# brushless.net
KiCad netlist of a schematic drawn in Altium Designer
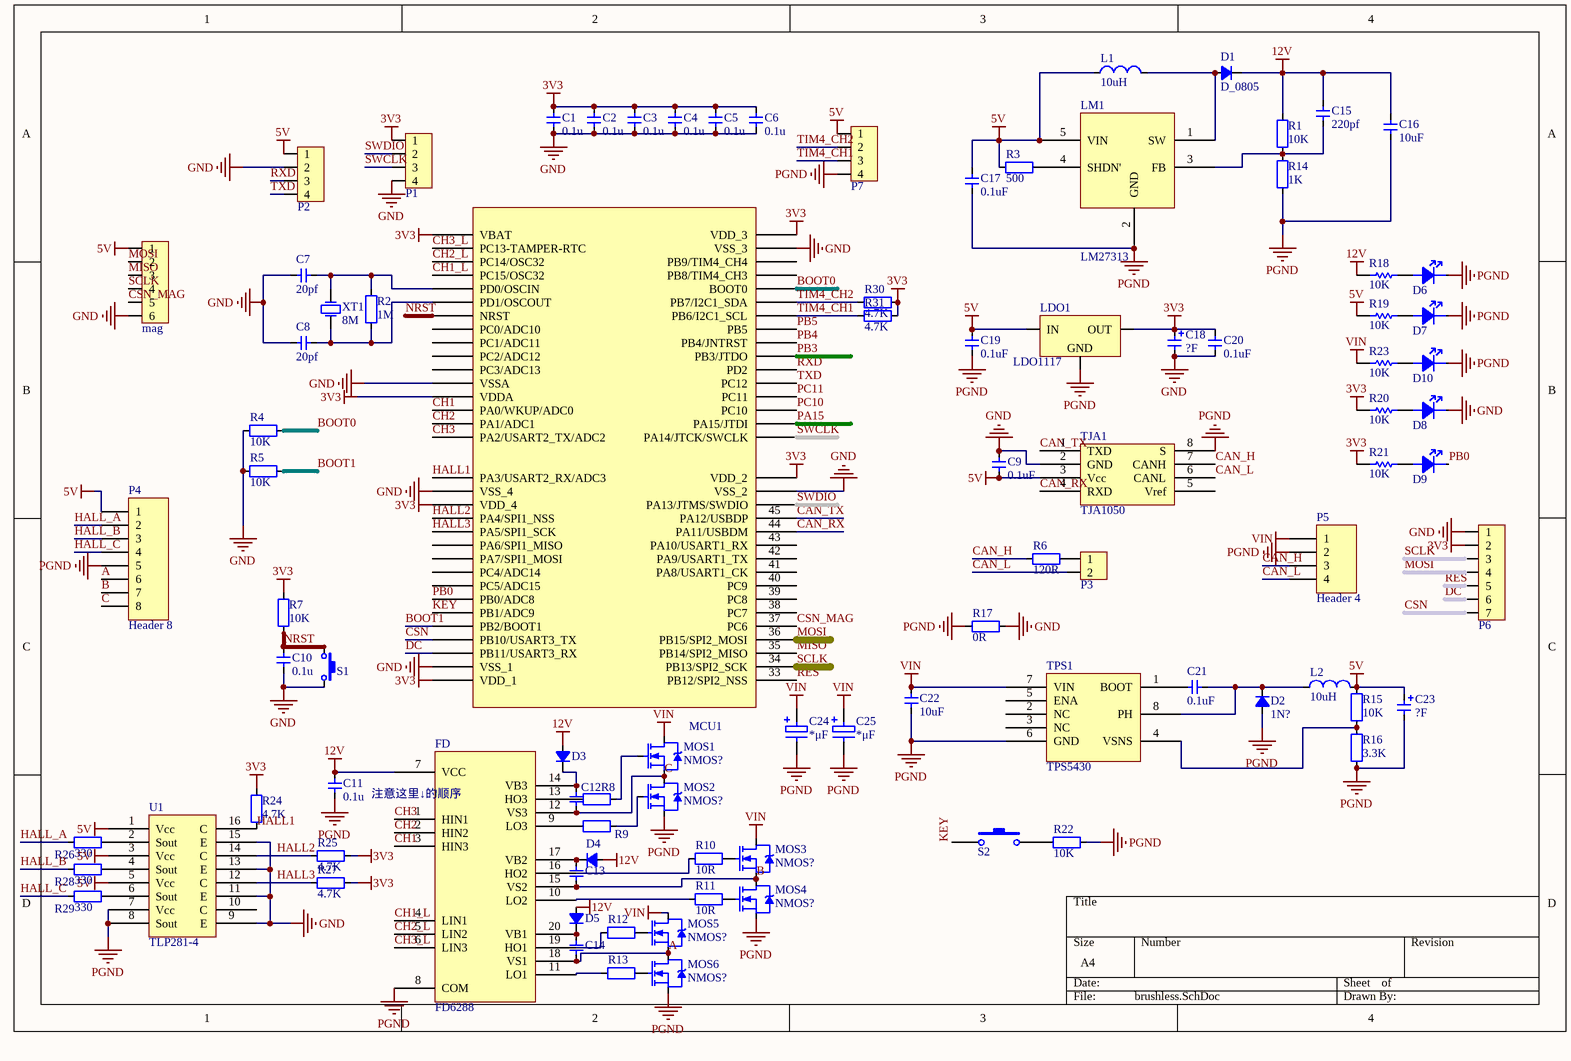
[diagram p0: brushless.SchDoc]

(export (version "E")
  (design (tool "Eeschema 10.0.6"))
  (components
    (comp (ref "C1")
      (value "0.1u")
      (footprint "PCB_PassiveCap:CAP_0603")
      (description "Capacitor")
      (fields (field (name "Comment") "Cap_0603"))
      (libsource (lib "SCH_Passive") (part "Cap_0603"))
    )
    (comp (ref "C2")
      (value "0.1u")
      (footprint "PCB_PassiveCap:CAP_0603")
      (description "Capacitor")
      (fields (field (name "Comment") "Cap_0603"))
      (libsource (lib "SCH_Passive") (part "Cap_0603"))
    )
    (comp (ref "C3")
      (value "0.1u")
      (footprint "PCB_PassiveCap:CAP_0603")
      (description "Capacitor")
      (fields (field (name "Comment") "Cap_0603"))
      (libsource (lib "SCH_Passive") (part "Cap_0603"))
    )
    (comp (ref "C4")
      (value "0.1u")
      (footprint "PCB_PassiveCap:CAP_0603")
      (description "Capacitor")
      (fields (field (name "Comment") "Cap_0603"))
      (libsource (lib "SCH_Passive") (part "Cap_0603"))
    )
    (comp (ref "C5")
      (value "0.1u")
      (footprint "PCB_PassiveCap:CAP_0603")
      (description "Capacitor")
      (fields (field (name "Comment") "Cap_0603"))
      (libsource (lib "SCH_Passive") (part "Cap_0603"))
    )
    (comp (ref "C6")
      (value "0.1u")
      (footprint "PCB_PassiveCap:CAP_0603")
      (description "Capacitor")
      (fields (field (name "Comment") "Cap_0603"))
      (libsource (lib "SCH_Passive") (part "Cap_0603"))
    )
    (comp (ref "C7")
      (value "20pf")
      (footprint "PCB_PassiveCap:CAP_0603")
      (description "Capacitor")
      (fields (field (name "Comment") "Cap_0603"))
      (libsource (lib "SCH_Passive") (part "Cap_0603"))
    )
    (comp (ref "C8")
      (value "20pf")
      (footprint "PCB_PassiveCap:CAP_0603")
      (description "Capacitor")
      (fields (field (name "Comment") "Cap_0603"))
      (libsource (lib "SCH_Passive") (part "Cap_0603"))
    )
    (comp (ref "C9")
      (value "0.1uF")
      (footprint "PCB_PassiveCap:CAP_0603")
      (description "Capacitor")
      (fields (field (name "Comment") "Cap_0603"))
      (libsource (lib "SCH_Passive") (part "Cap_0603"))
    )
    (comp (ref "C10")
      (value "0.1u")
      (footprint "PCB_PassiveCap:CAP_0603")
      (description "Capacitor")
      (fields (field (name "Comment") "Cap_0603"))
      (libsource (lib "SCH_Passive") (part "Cap_0603"))
    )
    (comp (ref "C11")
      (value "0.1u")
      (footprint "PCB_PassiveCap:CAP_0603")
      (description "Capacitor")
      (fields (field (name "Comment") "Cap_0603"))
      (libsource (lib "SCH_Passive") (part "Cap_0603"))
    )
    (comp (ref "C12")
      (value "Cap_0603")
      (footprint "PCB_PassiveCap:CAP_0603")
      (description "Capacitor")
      (libsource (lib "SCH_Passive") (part "Cap_0603"))
    )
    (comp (ref "C13")
      (value "Cap_0603")
      (footprint "PCB_PassiveCap:CAP_0603")
      (description "Capacitor")
      (libsource (lib "SCH_Passive") (part "Cap_0603"))
    )
    (comp (ref "C14")
      (value "Cap_0603")
      (footprint "PCB_PassiveCap:CAP_0603")
      (description "Capacitor")
      (libsource (lib "SCH_Passive") (part "Cap_0603"))
    )
    (comp (ref "C15")
      (value "220pf")
      (footprint "PCB_PassiveCap:CAP_0603")
      (description "Capacitor")
      (fields (field (name "Comment") "Cap_0603"))
      (libsource (lib "SCH_Passive") (part "Cap_0603"))
    )
    (comp (ref "C16")
      (value "10uF")
      (footprint "PCB_PassiveCap:CAP_0603")
      (description "Capacitor")
      (fields (field (name "Comment") "Cap_0603"))
      (libsource (lib "SCH_Passive") (part "Cap_0603"))
    )
    (comp (ref "C17")
      (value "0.1uF")
      (footprint "PCB_PassiveCap:CAP_0603")
      (description "Capacitor")
      (fields (field (name "Comment") "Cap_0603"))
      (libsource (lib "SCH_Passive") (part "Cap_0603"))
    )
    (comp (ref "C18")
      (value "?F")
      (footprint "PCB_PassiveCap:CAP_TAN_D2917")
      (description "Capacitor")
      (fields (field (name "Comment") "Cap_Tan_2917"))
      (libsource (lib "SCH_Passive") (part "Cap_Tan_2917"))
    )
    (comp (ref "C19")
      (value "0.1uF")
      (footprint "PCB_PassiveCap:CAP_0603")
      (description "Capacitor")
      (fields (field (name "Comment") "Cap_0603"))
      (libsource (lib "SCH_Passive") (part "Cap_0603"))
    )
    (comp (ref "C20")
      (value "0.1uF")
      (footprint "PCB_PassiveCap:CAP_0603")
      (description "Capacitor")
      (fields (field (name "Comment") "Cap_0603"))
      (libsource (lib "SCH_Passive") (part "Cap_0603"))
    )
    (comp (ref "C21")
      (value "0.1uF")
      (footprint "PCB_PassiveCap:CAP_0603")
      (description "Capacitor")
      (fields (field (name "Comment") "Cap_0603"))
      (libsource (lib "SCH_Passive") (part "Cap_0603"))
    )
    (comp (ref "C22")
      (value "10uF")
      (footprint "PCB_PassiveCap:CAP_0603")
      (description "Capacitor")
      (fields (field (name "Comment") "Cap_0603"))
      (libsource (lib "SCH_Passive") (part "Cap_0603"))
    )
    (comp (ref "C23")
      (value "?F")
      (footprint "PCB_PassiveCap:CAP_TAN_D2917")
      (description "Capacitor")
      (fields (field (name "Comment") "Cap_Tan_2917"))
      (libsource (lib "SCH_Passive") (part "Cap_Tan_2917"))
    )
    (comp (ref "C24")
      (value "*μF")
      (footprint "C_ELE2")
      (description "电解电容")
      (fields (field (name "PUBLISHER") "Altium Limited"))
      (libsource (lib "Libraries_2014_0618") (part "CAP-ELE"))
    )
    (comp (ref "C25")
      (value "*μF")
      (footprint "C_ELE2")
      (description "电解电容")
      (fields (field (name "PUBLISHER") "Altium Limited"))
      (libsource (lib "Libraries_2014_0618") (part "CAP-ELE"))
    )
    (comp (ref "D1")
      (value "D_0805")
      (footprint "LED_0805_YELLOW")
      (libsource (lib "SCH_Active") (part "D_0805"))
    )
    (comp (ref "D2")
      (value "1N?")
      (footprint "PCB_ActiveDIO:DO-214AC")
      (description "Diode")
      (fields (field (name "Comment") "Diode_SMA"))
      (libsource (lib "SCH_Active") (part "Diode_SMA"))
    )
    (comp (ref "D3")
      (value "D_0805")
      (footprint "LED_0805_YELLOW")
      (libsource (lib "SCH_Active") (part "D_0805"))
    )
    (comp (ref "D4")
      (value "D_0805")
      (footprint "LED_0805_YELLOW")
      (libsource (lib "SCH_Active") (part "D_0805"))
    )
    (comp (ref "D5")
      (value "D_0805")
      (footprint "LED_0805_YELLOW")
      (libsource (lib "SCH_Active") (part "D_0805"))
    )
    (comp (ref "D6")
      (value "lED")
      (footprint "0805D")
      (description "LED")
      (libsource (lib "K60-mainboard-v3.1") (part "00-D-LED"))
    )
    (comp (ref "D7")
      (value "lED")
      (footprint "0805D")
      (description "LED")
      (libsource (lib "K60-mainboard-v3.1") (part "00-D-LED"))
    )
    (comp (ref "D8")
      (value "lED")
      (footprint "0805D")
      (description "LED")
      (libsource (lib "K60-mainboard-v3.1") (part "00-D-LED"))
    )
    (comp (ref "D9")
      (value "lED")
      (footprint "0805D")
      (description "LED")
      (libsource (lib "K60-mainboard-v3.1") (part "00-D-LED"))
    )
    (comp (ref "D10")
      (value "lED")
      (footprint "0805D")
      (description "LED")
      (libsource (lib "K60-mainboard-v3.1") (part "00-D-LED"))
    )
    (comp (ref "FD")
      (value "FD6288")
      (footprint "TSSOP_E170_P0.65_20")
      (libsource (lib "SCH_IntegratedCircuit") (part "FD6288"))
    )
    (comp (ref "L1")
      (value "10uH")
      (footprint "IND_CD52")
      (description "Inductor")
      (fields (field (name "Comment") "Ind_CD32"))
      (libsource (lib "SCH_Passive") (part "Ind_CD32"))
    )
    (comp (ref "L2")
      (value "10uH")
      (footprint "IND_CD52")
      (description "Inductor")
      (fields (field (name "Comment") "Ind_CD32"))
      (libsource (lib "SCH_Passive") (part "Ind_CD32"))
    )
    (comp (ref "LDO1")
      (value "LDO1117")
      (footprint "PCB_IntegratedCircuit:SOT223-3")
      (description "Power")
      (libsource (lib "SCH_IntegratedCircuit") (part "LDO1117"))
    )
    (comp (ref "LM1")
      (value "LM27313")
      (footprint "SOT23-5")
      (libsource (lib "SCH_IntegratedCircuit") (part "LM27313"))
    )
    (comp (ref "mag")
      (value "HDR1x6_2.54")
      (footprint "PCB_ConnectorHDR:HDR1X6_2.54_180")
      (description "Header")
      (libsource (lib "SCH_ConnectorHDR") (part "HDR1x6_2.54"))
    )
    (comp (ref "MCU1")
      (value "STM32F103RC")
      (footprint "LQFP_P0.5_64")
      (description "MCU")
      (libsource (lib "SCH_IntegratedCircuit") (part "STM32F103RC"))
    )
    (comp (ref "MOS1")
      (value "NMOS?")
      (footprint "PCB_IntegratedCircuit:TO-252AA")
      (description "MOSFET")
      (fields (field (name "Comment") "MOSFET_N"))
      (libsource (lib "SCH_Active") (part "MOSFET_N"))
    )
    (comp (ref "MOS2")
      (value "NMOS?")
      (footprint "PCB_IntegratedCircuit:TO-252AA")
      (description "MOSFET")
      (fields (field (name "Comment") "MOSFET_N"))
      (libsource (lib "SCH_Active") (part "MOSFET_N"))
    )
    (comp (ref "MOS3")
      (value "NMOS?")
      (footprint "PCB_IntegratedCircuit:TO-252AA")
      (description "MOSFET")
      (fields (field (name "Comment") "MOSFET_N"))
      (libsource (lib "SCH_Active") (part "MOSFET_N"))
    )
    (comp (ref "MOS4")
      (value "NMOS?")
      (footprint "PCB_IntegratedCircuit:TO-252AA")
      (description "MOSFET")
      (fields (field (name "Comment") "MOSFET_N"))
      (libsource (lib "SCH_Active") (part "MOSFET_N"))
    )
    (comp (ref "MOS5")
      (value "NMOS?")
      (footprint "PCB_IntegratedCircuit:TO-252AA")
      (description "MOSFET")
      (fields (field (name "Comment") "MOSFET_N"))
      (libsource (lib "SCH_Active") (part "MOSFET_N"))
    )
    (comp (ref "MOS6")
      (value "NMOS?")
      (footprint "PCB_IntegratedCircuit:TO-252AA")
      (description "MOSFET")
      (fields (field (name "Comment") "MOSFET_N"))
      (libsource (lib "SCH_Active") (part "MOSFET_N"))
    )
    (comp (ref "P1")
      (value "HDR1x4_2.54")
      (footprint "PCB_ConnectorHDR:HDR1x4_2.54_180")
      (description "Header")
      (libsource (lib "SCH_ConnectorHDR") (part "HDR1x4_2.54"))
    )
    (comp (ref "P2")
      (value "HDR1x4_2.54")
      (footprint "PCB_ConnectorHDR:HDR1x4_2.54_180")
      (description "Header")
      (libsource (lib "SCH_ConnectorHDR") (part "HDR1x4_2.54"))
    )
    (comp (ref "P3")
      (value "HDR1x2_2.54")
      (footprint "PCB_ConnectorHDR:HDR1X2_2.54_180")
      (description "Header")
      (libsource (lib "SCH_ConnectorHDR") (part "HDR1x2_2.54"))
    )
    (comp (ref "P4")
      (value "Header 8")
      (footprint "Green_8P")
      (description "Header, 8-Pin")
      (fields (field (name "PUBLISHER") "Altium Limited"))
      (libsource (lib "Libraries_2014_0618") (part "Header 8"))
    )
    (comp (ref "P5")
      (value "Header 4")
      (footprint "Green_4P")
      (description "Header, 4-Pin")
      (fields (field (name "PUBLISHER") "Altium Limited"))
      (libsource (lib "Libraries_2014_0618") (part "Header 4"))
    )
    (comp (ref "P6")
      (value "HDR1x7_2.54")
      (footprint "PCB_ConnectorHDR:HDR1X7_2.54_180")
      (description "Header")
      (libsource (lib "SCH_ConnectorHDR") (part "HDR1x7_2.54T"))
    )
    (comp (ref "P7")
      (value "HDR1x4_2.54")
      (footprint "PCB_ConnectorHDR:HDR1x4_2.54_180")
      (description "Header")
      (libsource (lib "SCH_ConnectorHDR") (part "HDR1x4_2.54"))
    )
    (comp (ref "R1")
      (value "10K")
      (footprint "PCB_PassiveRes:RES_0603")
      (description "Resistor")
      (fields (field (name "Comment") "Res_0603"))
      (libsource (lib "") (part "Res_0603_3"))
    )
    (comp (ref "R2")
      (value "1M")
      (footprint "PCB_PassiveRes:RES_0603")
      (description "Resistor")
      (fields (field (name "Comment") "Res_0603"))
      (libsource (lib "") (part "Res_0603_2"))
    )
    (comp (ref "R3")
      (value "500")
      (footprint "PCB_PassiveRes:RES_0603")
      (description "Resistor")
      (fields (field (name "Comment") "Res_0603"))
      (libsource (lib "") (part "Res_0603_1"))
    )
    (comp (ref "R4")
      (value "10K")
      (footprint "PCB_PassiveRes:RES_0603")
      (description "Resistor")
      (fields (field (name "Comment") "Res_0603"))
      (libsource (lib "") (part "Res_0603_1"))
    )
    (comp (ref "R5")
      (value "10K")
      (footprint "PCB_PassiveRes:RES_0603")
      (description "Resistor")
      (fields (field (name "Comment") "Res_0603"))
      (libsource (lib "") (part "Res_0603_1"))
    )
    (comp (ref "R6")
      (value "120R")
      (footprint "PCB_PassiveRes:RES_0603")
      (description "Resistor")
      (fields (field (name "Comment") "Res_0603"))
      (libsource (lib "") (part "Res_0603_1"))
    )
    (comp (ref "R7")
      (value "10K")
      (footprint "PCB_PassiveRes:RES_0603")
      (description "Resistor")
      (fields (field (name "Comment") "Res_0603"))
      (libsource (lib "") (part "Res_0603_3"))
    )
    (comp (ref "R8")
      (value "Res_0603")
      (footprint "PCB_PassiveRes:RES_0603")
      (description "Resistor")
      (libsource (lib "SCH_Passive") (part "Res_0603"))
    )
    (comp (ref "R9")
      (value "Res_0603")
      (footprint "PCB_PassiveRes:RES_0603")
      (description "Resistor")
      (libsource (lib "SCH_Passive") (part "Res_0603"))
    )
    (comp (ref "R10")
      (value "10R")
      (footprint "PCB_PassiveRes:RES_0603")
      (description "Resistor")
      (fields (field (name "Comment") "Res_0603"))
      (libsource (lib "SCH_Passive") (part "Res_0603"))
    )
    (comp (ref "R11")
      (value "10R")
      (footprint "PCB_PassiveRes:RES_0603")
      (description "Resistor")
      (fields (field (name "Comment") "Res_0603"))
      (libsource (lib "SCH_Passive") (part "Res_0603"))
    )
    (comp (ref "R12")
      (value "Res_0603")
      (footprint "PCB_PassiveRes:RES_0603")
      (description "Resistor")
      (libsource (lib "SCH_Passive") (part "Res_0603"))
    )
    (comp (ref "R13")
      (value "Res_0603")
      (footprint "PCB_PassiveRes:RES_0603")
      (description "Resistor")
      (libsource (lib "SCH_Passive") (part "Res_0603"))
    )
    (comp (ref "R14")
      (value "1K")
      (footprint "PCB_PassiveRes:RES_0603")
      (description "Resistor")
      (fields (field (name "Comment") "Res_0603"))
      (libsource (lib "") (part "Res_0603_3"))
    )
    (comp (ref "R15")
      (value "10K")
      (footprint "PCB_PassiveRes:RES_0603")
      (description "Resistor")
      (fields (field (name "Comment") "Res_0603"))
      (libsource (lib "") (part "Res_0603_2"))
    )
    (comp (ref "R16")
      (value "3.3K")
      (footprint "PCB_PassiveRes:RES_0603")
      (description "Resistor")
      (fields (field (name "Comment") "Res_0603"))
      (libsource (lib "") (part "Res_0603_2"))
    )
    (comp (ref "R17")
      (value "0R")
      (footprint "PCB_PassiveRes:RES_0603")
      (description "Resistor")
      (fields (field (name "Comment") "Res_0603"))
      (libsource (lib "") (part "Res_0603_1"))
    )
    (comp (ref "R18")
      (value "10K")
      (footprint "RES-0603")
      (description "Resistor")
      (fields (field (name "Comment") "Res1") (field (name "PUBLISHER") "Altium Limited"))
      (libsource (lib "K60-mainboard-v3.1") (part "Res1_1"))
    )
    (comp (ref "R19")
      (value "10K")
      (footprint "RES-0603")
      (description "Resistor")
      (fields (field (name "Comment") "Res1") (field (name "PUBLISHER") "Altium Limited"))
      (libsource (lib "K60-mainboard-v3.1") (part "Res1_1"))
    )
    (comp (ref "R20")
      (value "10K")
      (footprint "RES-0603")
      (description "Resistor")
      (fields (field (name "Comment") "Res1") (field (name "PUBLISHER") "Altium Limited"))
      (libsource (lib "K60-mainboard-v3.1") (part "Res1_1"))
    )
    (comp (ref "R21")
      (value "10K")
      (footprint "RES-0603")
      (description "Resistor")
      (fields (field (name "Comment") "Res1") (field (name "PUBLISHER") "Altium Limited"))
      (libsource (lib "K60-mainboard-v3.1") (part "Res1_1"))
    )
    (comp (ref "R22")
      (value "10K")
      (footprint "PCB_PassiveRes:RES_0603")
      (description "Resistor")
      (fields (field (name "Comment") "Res_0603"))
      (libsource (lib "SCH_Passive") (part "Res_0603"))
    )
    (comp (ref "R23")
      (value "10K")
      (footprint "RES-0603")
      (description "Resistor")
      (fields (field (name "Comment") "Res1") (field (name "PUBLISHER") "Altium Limited"))
      (libsource (lib "K60-mainboard-v3.1") (part "Res1_1"))
    )
    (comp (ref "R24")
      (value "4.7K")
      (footprint "PCB_PassiveRes:RES_0603")
      (description "Resistor")
      (fields (field (name "Comment") "Res_0603"))
      (libsource (lib "") (part "Res_0603_2"))
    )
    (comp (ref "R25")
      (value "4.7K")
      (footprint "PCB_PassiveRes:RES_0603")
      (description "Resistor")
      (fields (field (name "Comment") "Res_0603"))
      (libsource (lib "") (part "Res_0603_1"))
    )
    (comp (ref "R26")
      (value "330")
      (footprint "PCB_PassiveRes:RES_0603")
      (description "Resistor")
      (fields (field (name "Comment") "Res_0603"))
      (libsource (lib "SCH_Passive") (part "Res_0603"))
    )
    (comp (ref "R27")
      (value "4.7K")
      (footprint "PCB_PassiveRes:RES_0603")
      (description "Resistor")
      (fields (field (name "Comment") "Res_0603"))
      (libsource (lib "") (part "Res_0603_1"))
    )
    (comp (ref "R28")
      (value "330")
      (footprint "PCB_PassiveRes:RES_0603")
      (description "Resistor")
      (fields (field (name "Comment") "Res_0603"))
      (libsource (lib "SCH_Passive") (part "Res_0603"))
    )
    (comp (ref "R29")
      (value "330")
      (footprint "PCB_PassiveRes:RES_0603")
      (description "Resistor")
      (fields (field (name "Comment") "Res_0603"))
      (libsource (lib "SCH_Passive") (part "Res_0603"))
    )
    (comp (ref "R30")
      (value "4.7K")
      (footprint "PCB_PassiveRes:RES_0603")
      (description "Resistor")
      (fields (field (name "Comment") "Res_0603"))
      (libsource (lib "") (part "Res_0603_1"))
    )
    (comp (ref "R31")
      (value "4.7K")
      (footprint "PCB_PassiveRes:RES_0603")
      (description "Resistor")
      (fields (field (name "Comment") "Res_0603"))
      (libsource (lib "") (part "Res_0603_1"))
    )
    (comp (ref "S1")
      (value "ButtonTACT_3x4x2_180")
      (footprint "PCB_Switch:ButtonTACT_3x4x2_180H")
      (description "Button")
      (libsource (lib "SCH_Switch") (part "ButtonTACT_3x4x2_180"))
    )
    (comp (ref "S2")
      (value "SW-PB")
      (footprint "key - duplicate")
      (description "Switch")
      (fields (field (name "PUBLISHER") "Altium Limited"))
      (libsource (lib "附加元件") (part "SW-PB"))
    )
    (comp (ref "TJA1")
      (value "TJA1050")
      (footprint "SOP_E150_8")
      (libsource (lib "SCH_IntegratedCircuit") (part "TJA1050"))
    )
    (comp (ref "TPS1")
      (value "TPS5430")
      (footprint "SOP_E150_8")
      (libsource (lib "SCH_IntegratedCircuit") (part "TPS5430"))
    )
    (comp (ref "U1")
      (value "TLP281-4")
      (footprint "SOP127P700X210-16N")
      (libsource (lib "Libraries_2014_0618") (part "IC-TLP281-4"))
    )
    (comp (ref "XT1")
      (value "8M")
      (footprint "PCB_Oscillator:XT_5032_2")
      (description "Crystal Oscillator")
      (fields (field (name "Comment") "XTAL_5032_2P"))
      (libsource (lib "SCH_Oscillator") (part "XTAL_5032_2P"))
    )
  )
  (nets
    (net (code "1") (name "/A") (class "Default")
      (node (ref "C14") (pin "2") (pinfunction "2_2") (pintype "passive"))
      (node (ref "FD") (pin "18") (pinfunction "VS1_18") (pintype "passive"))
      (node (ref "MOS5") (pin "3") (pinfunction "S_3") (pintype "passive"))
      (node (ref "MOS6") (pin "4") (pinfunction "D_4") (pintype "passive"))
      (node (ref "P4") (pin "6") (pinfunction "6_6") (pintype "passive"))
    )
    (net (code "2") (name "/B") (class "Default")
      (node (ref "C13") (pin "2") (pinfunction "2_2") (pintype "passive"))
      (node (ref "FD") (pin "15") (pinfunction "VS2_15") (pintype "passive"))
      (node (ref "MOS3") (pin "3") (pinfunction "S_3") (pintype "passive"))
      (node (ref "MOS4") (pin "4") (pinfunction "D_4") (pintype "passive"))
      (node (ref "P4") (pin "7") (pinfunction "7_7") (pintype "passive"))
    )
    (net (code "3") (name "/BOOT0") (class "Default")
      (node (ref "MCU1") (pin "60") (pinfunction "BOOT0_60") (pintype "passive"))
      (node (ref "R4") (pin "1") (pinfunction "1_1") (pintype "passive"))
    )
    (net (code "4") (name "/BOOT1") (class "Default")
      (node (ref "MCU1") (pin "28") (pinfunction "PB2/BOOT1_28") (pintype "passive"))
      (node (ref "R5") (pin "1") (pinfunction "1_1") (pintype "passive"))
    )
    (net (code "5") (name "/C") (class "Default")
      (node (ref "C12") (pin "2") (pinfunction "2_2") (pintype "passive"))
      (node (ref "FD") (pin "12") (pinfunction "VS3_12") (pintype "passive"))
      (node (ref "MOS1") (pin "3") (pinfunction "S_3") (pintype "passive"))
      (node (ref "MOS2") (pin "4") (pinfunction "D_4") (pintype "passive"))
      (node (ref "P4") (pin "8") (pinfunction "8_8") (pintype "passive"))
    )
    (net (code "6") (name "/CAN_H") (class "Default")
      (node (ref "P5") (pin "3") (pinfunction "3_3") (pintype "passive"))
      (node (ref "R6") (pin "2") (pinfunction "2_2") (pintype "passive"))
      (node (ref "TJA1") (pin "7") (pinfunction "CANH_7") (pintype "passive"))
    )
    (net (code "7") (name "/CAN_L") (class "Default")
      (node (ref "P3") (pin "2") (pinfunction "2_2") (pintype "passive"))
      (node (ref "P5") (pin "4") (pinfunction "4_4") (pintype "passive"))
      (node (ref "TJA1") (pin "6") (pinfunction "CANL_6") (pintype "passive"))
    )
    (net (code "8") (name "/CAN_RX") (class "Default")
      (node (ref "MCU1") (pin "44") (pinfunction "PA11/USBDM_44") (pintype "passive"))
      (node (ref "TJA1") (pin "4") (pinfunction "RXD_4") (pintype "passive"))
    )
    (net (code "9") (name "/CAN_TX") (class "Default")
      (node (ref "MCU1") (pin "45") (pinfunction "PA12/USBDP_45") (pintype "passive"))
      (node (ref "TJA1") (pin "1") (pinfunction "TXD_1") (pintype "passive"))
    )
    (net (code "10") (name "/CH1") (class "Default")
      (node (ref "FD") (pin "3") (pinfunction "HIN3_3") (pintype "passive"))
      (node (ref "MCU1") (pin "14") (pinfunction "PA0/WKUP/ADC0_14") (pintype "passive"))
    )
    (net (code "11") (name "/CH1_L") (class "Default")
      (node (ref "FD") (pin "4") (pinfunction "LIN1_4") (pintype "passive"))
      (node (ref "MCU1") (pin "4") (pinfunction "PC15/OSC32_4") (pintype "passive"))
    )
    (net (code "12") (name "/CH2") (class "Default")
      (node (ref "FD") (pin "2") (pinfunction "HIN2_2") (pintype "passive"))
      (node (ref "MCU1") (pin "15") (pinfunction "PA1/ADC1_15") (pintype "passive"))
    )
    (net (code "13") (name "/CH2_L") (class "Default")
      (node (ref "FD") (pin "5") (pinfunction "LIN2_5") (pintype "passive"))
      (node (ref "MCU1") (pin "3") (pinfunction "PC14/OSC32_3") (pintype "passive"))
    )
    (net (code "14") (name "/CH3") (class "Default")
      (node (ref "FD") (pin "1") (pinfunction "HIN1_1") (pintype "passive"))
      (node (ref "MCU1") (pin "16") (pinfunction "PA2/USART2_TX/ADC2_16") (pintype "passive"))
    )
    (net (code "15") (name "/CH3_L") (class "Default")
      (node (ref "FD") (pin "6") (pinfunction "LIN3_6") (pintype "passive"))
      (node (ref "MCU1") (pin "2") (pinfunction "PC13-TAMPER-RTC_2") (pintype "passive"))
    )
    (net (code "16") (name "/CSN") (class "Default")
      (node (ref "MCU1") (pin "29") (pinfunction "PB10/USART3_TX_29") (pintype "passive"))
      (node (ref "P6") (pin "7") (pinfunction "7_7") (pintype "passive"))
    )
    (net (code "17") (name "/CSN_MAG") (class "Default")
      (node (ref "MCU1") (pin "37") (pinfunction "PC6_37") (pintype "passive"))
      (node (ref "mag") (pin "5") (pinfunction "5_5") (pintype "passive"))
    )
    (net (code "18") (name "/DC") (class "Default")
      (node (ref "MCU1") (pin "30") (pinfunction "PB11/USART3_RX_30") (pintype "passive"))
      (node (ref "P6") (pin "6") (pinfunction "6_6") (pintype "passive"))
    )
    (net (code "19") (name "/HALL1") (class "Default")
      (node (ref "MCU1") (pin "17") (pinfunction "PA3/USART2_RX/ADC3_17") (pintype "passive"))
      (node (ref "R24") (pin "1") (pinfunction "1_1") (pintype "passive"))
      (node (ref "U1") (pin "16") (pinfunction "C_16") (pintype "power_in"))
    )
    (net (code "20") (name "/HALL2") (class "Default")
      (node (ref "MCU1") (pin "20") (pinfunction "PA4/SPI1_NSS_20") (pintype "passive"))
      (node (ref "R25") (pin "2") (pinfunction "2_2") (pintype "passive"))
      (node (ref "U1") (pin "14") (pinfunction "C_14") (pintype "power_in"))
    )
    (net (code "21") (name "/HALL3") (class "Default")
      (node (ref "MCU1") (pin "21") (pinfunction "PA5/SPI1_SCK_21") (pintype "passive"))
      (node (ref "R27") (pin "2") (pinfunction "2_2") (pintype "passive"))
      (node (ref "U1") (pin "12") (pinfunction "C_12") (pintype "power_in"))
    )
    (net (code "22") (name "/HALL_A") (class "Default")
      (node (ref "P4") (pin "2") (pinfunction "2_2") (pintype "passive"))
      (node (ref "R26") (pin "1") (pinfunction "1_1") (pintype "passive"))
    )
    (net (code "23") (name "/HALL_B") (class "Default")
      (node (ref "P4") (pin "3") (pinfunction "3_3") (pintype "passive"))
      (node (ref "R28") (pin "1") (pinfunction "1_1") (pintype "passive"))
    )
    (net (code "24") (name "/HALL_C") (class "Default")
      (node (ref "P4") (pin "4") (pinfunction "4_4") (pintype "passive"))
      (node (ref "R29") (pin "1") (pinfunction "1_1") (pintype "passive"))
    )
    (net (code "25") (name "/KEY") (class "Default")
      (node (ref "MCU1") (pin "27") (pinfunction "PB1/ADC9_27") (pintype "passive"))
      (node (ref "S2") (pin "1") (pinfunction "1_1") (pintype "passive"))
    )
    (net (code "26") (name "/MISO") (class "Default")
      (node (ref "MCU1") (pin "35") (pinfunction "PB14/SPI2_MISO_35") (pintype "passive"))
      (node (ref "mag") (pin "3") (pinfunction "3_3") (pintype "passive"))
    )
    (net (code "27") (name "/MOSI") (class "Default")
      (node (ref "MCU1") (pin "36") (pinfunction "PB15/SPI2_MOSI_36") (pintype "passive"))
      (node (ref "P6") (pin "4") (pinfunction "4_4") (pintype "passive"))
      (node (ref "mag") (pin "2") (pinfunction "2_2") (pintype "passive"))
    )
    (net (code "28") (name "/NRST") (class "Default")
      (node (ref "C10") (pin "2") (pinfunction "2_2") (pintype "passive"))
      (node (ref "MCU1") (pin "7") (pinfunction "NRST_7") (pintype "passive"))
      (node (ref "R7") (pin "2") (pinfunction "2_2") (pintype "passive"))
      (node (ref "S1") (pin "1") (pinfunction "1_1") (pintype "passive"))
    )
    (net (code "29") (name "/PA15") (class "Default")
      (node (ref "MCU1") (pin "50") (pinfunction "PA15/JTDI_50") (pintype "passive"))
    )
    (net (code "30") (name "/PB0") (class "Default")
      (node (ref "D9") (pin "K") (pinfunction "2_K") (pintype "passive"))
      (node (ref "MCU1") (pin "26") (pinfunction "PB0/ADC8_26") (pintype "passive"))
    )
    (net (code "31") (name "/PB3") (class "Default")
      (node (ref "MCU1") (pin "55") (pinfunction "PB3/JTDO_55") (pintype "passive"))
    )
    (net (code "32") (name "/PB4") (class "Default")
      (node (ref "MCU1") (pin "56") (pinfunction "PB4/JNTRST_56") (pintype "passive"))
    )
    (net (code "33") (name "/PB5") (class "Default")
      (node (ref "MCU1") (pin "57") (pinfunction "PB5_57") (pintype "passive"))
    )
    (net (code "34") (name "/PC10") (class "Default")
      (node (ref "MCU1") (pin "51") (pinfunction "PC10_51") (pintype "passive"))
    )
    (net (code "35") (name "/PC11") (class "Default")
      (node (ref "MCU1") (pin "52") (pinfunction "PC11_52") (pintype "passive"))
    )
    (net (code "36") (name "/RES") (class "Default")
      (node (ref "MCU1") (pin "33") (pinfunction "PB12/SPI2_NSS_33") (pintype "passive"))
      (node (ref "P6") (pin "5") (pinfunction "5_5") (pintype "passive"))
    )
    (net (code "37") (name "/RXD") (class "Default")
      (node (ref "MCU1") (pin "54") (pinfunction "PD2_54") (pintype "passive"))
      (node (ref "P2") (pin "3") (pinfunction "3_3") (pintype "passive"))
    )
    (net (code "38") (name "/SCLK") (class "Default")
      (node (ref "MCU1") (pin "34") (pinfunction "PB13/SPI2_SCK_34") (pintype "passive"))
      (node (ref "P6") (pin "3") (pinfunction "3_3") (pintype "passive"))
      (node (ref "mag") (pin "4") (pinfunction "4_4") (pintype "passive"))
    )
    (net (code "39") (name "/SWCLK") (class "Default")
      (node (ref "MCU1") (pin "49") (pinfunction "PA14/JTCK/SWCLK_49") (pintype "passive"))
      (node (ref "P1") (pin "3") (pinfunction "3_3") (pintype "passive"))
    )
    (net (code "40") (name "/SWDIO") (class "Default")
      (node (ref "MCU1") (pin "46") (pinfunction "PA13/JTMS/SWDIO_46") (pintype "passive"))
      (node (ref "P1") (pin "2") (pinfunction "2_2") (pintype "passive"))
    )
    (net (code "41") (name "/TIM4_CH1") (class "Default")
      (node (ref "MCU1") (pin "58") (pinfunction "PB6/I2C1_SCL_58") (pintype "passive"))
      (node (ref "P7") (pin "3") (pinfunction "3_3") (pintype "passive"))
      (node (ref "R31") (pin "2") (pinfunction "2_2") (pintype "passive"))
    )
    (net (code "42") (name "/TIM4_CH2") (class "Default")
      (node (ref "MCU1") (pin "59") (pinfunction "PB7/I2C1_SDA_59") (pintype "passive"))
      (node (ref "P7") (pin "2") (pinfunction "2_2") (pintype "passive"))
      (node (ref "R30") (pin "2") (pinfunction "2_2") (pintype "passive"))
    )
    (net (code "43") (name "/TXD") (class "Default")
      (node (ref "MCU1") (pin "53") (pinfunction "PC12_53") (pintype "passive"))
      (node (ref "P2") (pin "4") (pinfunction "4_4") (pintype "passive"))
    )
    (net (code "44") (name "3V3") (class "Default")
      (node (ref "C1") (pin "2") (pinfunction "2_2") (pintype "passive"))
      (node (ref "C18") (pin "1") (pinfunction "1_1") (pintype "passive"))
      (node (ref "C2") (pin "2") (pinfunction "2_2") (pintype "passive"))
      (node (ref "C20") (pin "1") (pinfunction "1_1") (pintype "passive"))
      (node (ref "C3") (pin "2") (pinfunction "2_2") (pintype "passive"))
      (node (ref "C4") (pin "2") (pinfunction "2_2") (pintype "passive"))
      (node (ref "C5") (pin "2") (pinfunction "2_2") (pintype "passive"))
      (node (ref "C6") (pin "2") (pinfunction "2_2") (pintype "passive"))
      (node (ref "LDO1") (pin "2") (pinfunction "OUT_2") (pintype "power_in"))
      (node (ref "MCU1") (pin "1") (pinfunction "VBAT_1") (pintype "passive"))
      (node (ref "MCU1") (pin "13") (pinfunction "VDDA_13") (pintype "passive"))
      (node (ref "MCU1") (pin "19") (pinfunction "VDD_4_19") (pintype "passive"))
      (node (ref "MCU1") (pin "32") (pinfunction "VDD_1_32") (pintype "passive"))
      (node (ref "MCU1") (pin "48") (pinfunction "VDD_2_48") (pintype "passive"))
      (node (ref "MCU1") (pin "64") (pinfunction "VDD_3_64") (pintype "passive"))
      (node (ref "P1") (pin "1") (pinfunction "1_1") (pintype "passive"))
      (node (ref "P6") (pin "2") (pinfunction "2_2") (pintype "passive"))
      (node (ref "R20") (pin "2") (pinfunction "2_2") (pintype "passive"))
      (node (ref "R21") (pin "2") (pinfunction "2_2") (pintype "passive"))
      (node (ref "R24") (pin "2") (pinfunction "2_2") (pintype "passive"))
      (node (ref "R25") (pin "1") (pinfunction "1_1") (pintype "passive"))
      (node (ref "R27") (pin "1") (pinfunction "1_1") (pintype "passive"))
      (node (ref "R30") (pin "1") (pinfunction "1_1") (pintype "passive"))
      (node (ref "R31") (pin "1") (pinfunction "1_1") (pintype "passive"))
      (node (ref "R7") (pin "1") (pinfunction "1_1") (pintype "passive"))
    )
    (net (code "45") (name "5V") (class "Default")
      (node (ref "C17") (pin "1") (pinfunction "1_1") (pintype "passive"))
      (node (ref "C19") (pin "1") (pinfunction "1_1") (pintype "passive"))
      (node (ref "C23") (pin "1") (pinfunction "1_1") (pintype "passive"))
      (node (ref "C9") (pin "1") (pinfunction "1_1") (pintype "passive"))
      (node (ref "L1") (pin "1") (pinfunction "1_1") (pintype "passive"))
      (node (ref "L2") (pin "2") (pinfunction "2_2") (pintype "passive"))
      (node (ref "LDO1") (pin "3") (pinfunction "IN_3") (pintype "power_in"))
      (node (ref "LM1") (pin "5") (pinfunction "VIN_5") (pintype "passive"))
      (node (ref "P2") (pin "1") (pinfunction "1_1") (pintype "passive"))
      (node (ref "P4") (pin "1") (pinfunction "1_1") (pintype "passive"))
      (node (ref "P7") (pin "1") (pinfunction "1_1") (pintype "passive"))
      (node (ref "R15") (pin "2") (pinfunction "2_2") (pintype "passive"))
      (node (ref "R19") (pin "2") (pinfunction "2_2") (pintype "passive"))
      (node (ref "R3") (pin "2") (pinfunction "2_2") (pintype "passive"))
      (node (ref "TJA1") (pin "3") (pinfunction "Vcc_3") (pintype "passive"))
      (node (ref "U1") (pin "1") (pinfunction "Vcc_1") (pintype "power_in"))
      (node (ref "U1") (pin "3") (pinfunction "Vcc_3") (pintype "power_in"))
      (node (ref "U1") (pin "5") (pinfunction "Vcc_5") (pintype "power_in"))
      (node (ref "mag") (pin "1") (pinfunction "1_1") (pintype "passive"))
    )
    (net (code "46") (name "12V") (class "Default")
      (node (ref "C11") (pin "2") (pinfunction "2_2") (pintype "passive"))
      (node (ref "C15") (pin "1") (pinfunction "1_1") (pintype "passive"))
      (node (ref "C16") (pin "2") (pinfunction "2_2") (pintype "passive"))
      (node (ref "D1") (pin "2") (pinfunction "K_2") (pintype "passive"))
      (node (ref "D3") (pin "1") (pinfunction "A_1") (pintype "passive"))
      (node (ref "D4") (pin "1") (pinfunction "A_1") (pintype "passive"))
      (node (ref "D5") (pin "1") (pinfunction "A_1") (pintype "passive"))
      (node (ref "FD") (pin "7") (pinfunction "VCC_7") (pintype "passive"))
      (node (ref "R1") (pin "1") (pinfunction "1_1") (pintype "passive"))
      (node (ref "R18") (pin "2") (pinfunction "2_2") (pintype "passive"))
    )
    (net (code "47") (name "GND") (class "Default")
      (node (ref "C1") (pin "1") (pinfunction "1_1") (pintype "passive"))
      (node (ref "C10") (pin "1") (pinfunction "1_1") (pintype "passive"))
      (node (ref "C18") (pin "2") (pinfunction "2_2") (pintype "passive"))
      (node (ref "C2") (pin "1") (pinfunction "1_1") (pintype "passive"))
      (node (ref "C20") (pin "2") (pinfunction "2_2") (pintype "passive"))
      (node (ref "C3") (pin "1") (pinfunction "1_1") (pintype "passive"))
      (node (ref "C4") (pin "1") (pinfunction "1_1") (pintype "passive"))
      (node (ref "C5") (pin "1") (pinfunction "1_1") (pintype "passive"))
      (node (ref "C6") (pin "1") (pinfunction "1_1") (pintype "passive"))
      (node (ref "C7") (pin "1") (pinfunction "1_1") (pintype "passive"))
      (node (ref "C8") (pin "1") (pinfunction "1_1") (pintype "passive"))
      (node (ref "C9") (pin "2") (pinfunction "2_2") (pintype "passive"))
      (node (ref "D8") (pin "K") (pinfunction "2_K") (pintype "passive"))
      (node (ref "MCU1") (pin "12") (pinfunction "VSSA_12") (pintype "passive"))
      (node (ref "MCU1") (pin "18") (pinfunction "VSS_4_18") (pintype "passive"))
      (node (ref "MCU1") (pin "31") (pinfunction "VSS_1_31") (pintype "passive"))
      (node (ref "MCU1") (pin "47") (pinfunction "VSS_2_47") (pintype "passive"))
      (node (ref "MCU1") (pin "63") (pinfunction "VSS_3_63") (pintype "passive"))
      (node (ref "P1") (pin "4") (pinfunction "4_4") (pintype "passive"))
      (node (ref "P2") (pin "2") (pinfunction "2_2") (pintype "passive"))
      (node (ref "P6") (pin "1") (pinfunction "1_1") (pintype "passive"))
      (node (ref "R17") (pin "1") (pinfunction "1_1") (pintype "passive"))
      (node (ref "R4") (pin "2") (pinfunction "2_2") (pintype "passive"))
      (node (ref "R5") (pin "2") (pinfunction "2_2") (pintype "passive"))
      (node (ref "S1") (pin "2") (pinfunction "2_2") (pintype "passive"))
      (node (ref "TJA1") (pin "2") (pinfunction "GND_2") (pintype "passive"))
      (node (ref "U1") (pin "11") (pinfunction "E_11") (pintype "power_in"))
      (node (ref "U1") (pin "13") (pinfunction "E_13") (pintype "power_in"))
      (node (ref "U1") (pin "15") (pinfunction "E_15") (pintype "power_in"))
      (node (ref "U1") (pin "9") (pinfunction "E_9") (pintype "power_in"))
      (node (ref "mag") (pin "6") (pinfunction "6_6") (pintype "passive"))
    )
    (net (code "48") (name "Net-(D1-A)") (class "Default")
      (node (ref "D1") (pin "1") (pinfunction "A_1") (pintype "passive"))
      (node (ref "L1") (pin "2") (pinfunction "2_2") (pintype "passive"))
      (node (ref "LM1") (pin "1") (pinfunction "SW_1") (pintype "passive"))
    )
    (net (code "49") (name "Net-(D2-K)") (class "Default")
      (node (ref "C21") (pin "1") (pinfunction "1_1") (pintype "passive"))
      (node (ref "D2") (pin "2") (pinfunction "K_2") (pintype "passive"))
      (node (ref "L2") (pin "1") (pinfunction "1_1") (pintype "passive"))
      (node (ref "TPS1") (pin "8") (pinfunction "PH_8") (pintype "passive"))
    )
    (net (code "50") (name "Net-(D3-K)") (class "Default")
      (node (ref "C12") (pin "1") (pinfunction "1_1") (pintype "passive"))
      (node (ref "D3") (pin "2") (pinfunction "K_2") (pintype "passive"))
      (node (ref "FD") (pin "14") (pinfunction "VB3_14") (pintype "passive"))
    )
    (net (code "51") (name "Net-(D4-K)") (class "Default")
      (node (ref "C13") (pin "1") (pinfunction "1_1") (pintype "passive"))
      (node (ref "D4") (pin "2") (pinfunction "K_2") (pintype "passive"))
      (node (ref "FD") (pin "17") (pinfunction "VB2_17") (pintype "passive"))
    )
    (net (code "52") (name "Net-(D5-K)") (class "Default")
      (node (ref "C14") (pin "1") (pinfunction "1_1") (pintype "passive"))
      (node (ref "D5") (pin "2") (pinfunction "K_2") (pintype "passive"))
      (node (ref "FD") (pin "20") (pinfunction "VB1_20") (pintype "passive"))
    )
    (net (code "53") (name "Net-(D6-1)") (class "Default")
      (node (ref "D6") (pin "A") (pinfunction "1_A") (pintype "passive"))
      (node (ref "R18") (pin "1") (pinfunction "1_1") (pintype "passive"))
    )
    (net (code "54") (name "Net-(D7-1)") (class "Default")
      (node (ref "D7") (pin "A") (pinfunction "1_A") (pintype "passive"))
      (node (ref "R19") (pin "1") (pinfunction "1_1") (pintype "passive"))
    )
    (net (code "55") (name "Net-(D8-1)") (class "Default")
      (node (ref "D8") (pin "A") (pinfunction "1_A") (pintype "passive"))
      (node (ref "R20") (pin "1") (pinfunction "1_1") (pintype "passive"))
    )
    (net (code "56") (name "Net-(D9-1)") (class "Default")
      (node (ref "D9") (pin "A") (pinfunction "1_A") (pintype "passive"))
      (node (ref "R21") (pin "1") (pinfunction "1_1") (pintype "passive"))
    )
    (net (code "57") (name "Net-(D10-1)") (class "Default")
      (node (ref "D10") (pin "A") (pinfunction "1_A") (pintype "passive"))
      (node (ref "R23") (pin "1") (pinfunction "1_1") (pintype "passive"))
    )
    (net (code "58") (name "Net-(FD-HO1)") (class "Default")
      (node (ref "FD") (pin "19") (pinfunction "HO1_19") (pintype "passive"))
      (node (ref "R12") (pin "1") (pinfunction "1_1") (pintype "passive"))
    )
    (net (code "59") (name "Net-(FD-HO2)") (class "Default")
      (node (ref "FD") (pin "16") (pinfunction "HO2_16") (pintype "passive"))
      (node (ref "R10") (pin "1") (pinfunction "1_1") (pintype "passive"))
    )
    (net (code "60") (name "Net-(FD-HO3)") (class "Default")
      (node (ref "FD") (pin "13") (pinfunction "HO3_13") (pintype "passive"))
      (node (ref "R8") (pin "1") (pinfunction "1_1") (pintype "passive"))
    )
    (net (code "61") (name "Net-(FD-LO1)") (class "Default")
      (node (ref "FD") (pin "11") (pinfunction "LO1_11") (pintype "passive"))
      (node (ref "R13") (pin "1") (pinfunction "1_1") (pintype "passive"))
    )
    (net (code "62") (name "Net-(FD-LO2)") (class "Default")
      (node (ref "FD") (pin "10") (pinfunction "LO2_10") (pintype "passive"))
      (node (ref "R11") (pin "1") (pinfunction "1_1") (pintype "passive"))
    )
    (net (code "63") (name "Net-(FD-LO3)") (class "Default")
      (node (ref "FD") (pin "9") (pinfunction "LO3_9") (pintype "passive"))
      (node (ref "R9") (pin "1") (pinfunction "1_1") (pintype "passive"))
    )
    (net (code "64") (name "Net-(LM1-FB)") (class "Default")
      (node (ref "C15") (pin "2") (pinfunction "2_2") (pintype "passive"))
      (node (ref "LM1") (pin "3") (pinfunction "FB_3") (pintype "passive"))
      (node (ref "R1") (pin "2") (pinfunction "2_2") (pintype "passive"))
      (node (ref "R14") (pin "1") (pinfunction "1_1") (pintype "passive"))
    )
    (net (code "65") (name "Net-(LM1-SHDN')") (class "Default")
      (node (ref "LM1") (pin "4") (pinfunction "SHDN'_4") (pintype "passive"))
      (node (ref "R3") (pin "1") (pinfunction "1_1") (pintype "passive"))
    )
    (net (code "66") (name "Net-(MCU1-PD0{slash}OSCIN)") (class "Default")
      (node (ref "C7") (pin "2") (pinfunction "2_2") (pintype "passive"))
      (node (ref "MCU1") (pin "5") (pinfunction "PD0/OSCIN_5") (pintype "passive"))
      (node (ref "R2") (pin "2") (pinfunction "2_2") (pintype "passive"))
      (node (ref "XT1") (pin "2") (pinfunction "OSC2_2") (pintype "passive"))
    )
    (net (code "67") (name "Net-(MCU1-PD1{slash}OSCOUT)") (class "Default")
      (node (ref "C8") (pin "2") (pinfunction "2_2") (pintype "passive"))
      (node (ref "MCU1") (pin "6") (pinfunction "PD1/OSCOUT_6") (pintype "passive"))
      (node (ref "R2") (pin "1") (pinfunction "1_1") (pintype "passive"))
      (node (ref "XT1") (pin "1") (pinfunction "OSC1_1") (pintype "passive"))
    )
    (net (code "68") (name "Net-(MOS1-G)") (class "Default")
      (node (ref "MOS1") (pin "1") (pinfunction "G_1") (pintype "passive"))
      (node (ref "R8") (pin "2") (pinfunction "2_2") (pintype "passive"))
    )
    (net (code "69") (name "Net-(MOS2-G)") (class "Default")
      (node (ref "MOS2") (pin "1") (pinfunction "G_1") (pintype "passive"))
      (node (ref "R9") (pin "2") (pinfunction "2_2") (pintype "passive"))
    )
    (net (code "70") (name "Net-(MOS3-G)") (class "Default")
      (node (ref "MOS3") (pin "1") (pinfunction "G_1") (pintype "passive"))
      (node (ref "R10") (pin "2") (pinfunction "2_2") (pintype "passive"))
    )
    (net (code "71") (name "Net-(MOS4-G)") (class "Default")
      (node (ref "MOS4") (pin "1") (pinfunction "G_1") (pintype "passive"))
      (node (ref "R11") (pin "2") (pinfunction "2_2") (pintype "passive"))
    )
    (net (code "72") (name "Net-(MOS5-G)") (class "Default")
      (node (ref "MOS5") (pin "1") (pinfunction "G_1") (pintype "passive"))
      (node (ref "R12") (pin "2") (pinfunction "2_2") (pintype "passive"))
    )
    (net (code "73") (name "Net-(MOS6-G)") (class "Default")
      (node (ref "MOS6") (pin "1") (pinfunction "G_1") (pintype "passive"))
      (node (ref "R13") (pin "2") (pinfunction "2_2") (pintype "passive"))
    )
    (net (code "74") (name "Net-(P3-Pad1)") (class "Default")
      (node (ref "P3") (pin "1") (pinfunction "1_1") (pintype "passive"))
      (node (ref "R6") (pin "1") (pinfunction "1_1") (pintype "passive"))
    )
    (net (code "75") (name "Net-(R22-Pad1)") (class "Default")
      (node (ref "R22") (pin "1") (pinfunction "1_1") (pintype "passive"))
      (node (ref "S2") (pin "2") (pinfunction "2_2") (pintype "passive"))
    )
    (net (code "76") (name "Net-(R26-Pad2)") (class "Default")
      (node (ref "R26") (pin "2") (pinfunction "2_2") (pintype "passive"))
      (node (ref "U1") (pin "2") (pinfunction "Sout_2") (pintype "power_in"))
    )
    (net (code "77") (name "Net-(R28-Pad2)") (class "Default")
      (node (ref "R28") (pin "2") (pinfunction "2_2") (pintype "passive"))
      (node (ref "U1") (pin "4") (pinfunction "Sout_4") (pintype "power_in"))
    )
    (net (code "78") (name "Net-(R29-Pad2)") (class "Default")
      (node (ref "R29") (pin "2") (pinfunction "2_2") (pintype "passive"))
      (node (ref "U1") (pin "6") (pinfunction "Sout_6") (pintype "power_in"))
    )
    (net (code "79") (name "Net-(TPS1-BOOT)") (class "Default")
      (node (ref "C21") (pin "2") (pinfunction "2_2") (pintype "passive"))
      (node (ref "TPS1") (pin "1") (pinfunction "BOOT_1") (pintype "passive"))
    )
    (net (code "80") (name "Net-(TPS1-VSNS)") (class "Default")
      (node (ref "R15") (pin "1") (pinfunction "1_1") (pintype "passive"))
      (node (ref "R16") (pin "2") (pinfunction "2_2") (pintype "passive"))
      (node (ref "TPS1") (pin "4") (pinfunction "VSNS_4") (pintype "passive"))
    )
    (net (code "81") (name "PGND") (class "Default")
      (node (ref "C11") (pin "1") (pinfunction "1_1") (pintype "passive"))
      (node (ref "C16") (pin "1") (pinfunction "1_1") (pintype "passive"))
      (node (ref "C17") (pin "2") (pinfunction "2_2") (pintype "passive"))
      (node (ref "C19") (pin "2") (pinfunction "2_2") (pintype "passive"))
      (node (ref "C22") (pin "2") (pinfunction "2_2") (pintype "passive"))
      (node (ref "C23") (pin "2") (pinfunction "2_2") (pintype "passive"))
      (node (ref "C24") (pin "2") (pinfunction "2_2") (pintype "passive"))
      (node (ref "C25") (pin "2") (pinfunction "2_2") (pintype "passive"))
      (node (ref "D10") (pin "K") (pinfunction "2_K") (pintype "passive"))
      (node (ref "D2") (pin "1") (pinfunction "A_1") (pintype "passive"))
      (node (ref "D6") (pin "K") (pinfunction "2_K") (pintype "passive"))
      (node (ref "D7") (pin "K") (pinfunction "2_K") (pintype "passive"))
      (node (ref "FD") (pin "8") (pinfunction "COM_8") (pintype "passive"))
      (node (ref "LDO1") (pin "1") (pinfunction "GND_1") (pintype "power_in"))
      (node (ref "LM1") (pin "2") (pinfunction "GND_2") (pintype "passive"))
      (node (ref "MOS2") (pin "3") (pinfunction "S_3") (pintype "passive"))
      (node (ref "MOS4") (pin "3") (pinfunction "S_3") (pintype "passive"))
      (node (ref "MOS6") (pin "3") (pinfunction "S_3") (pintype "passive"))
      (node (ref "P4") (pin "5") (pinfunction "5_5") (pintype "passive"))
      (node (ref "P5") (pin "2") (pinfunction "2_2") (pintype "passive"))
      (node (ref "P7") (pin "4") (pinfunction "4_4") (pintype "passive"))
      (node (ref "R14") (pin "2") (pinfunction "2_2") (pintype "passive"))
      (node (ref "R16") (pin "1") (pinfunction "1_1") (pintype "passive"))
      (node (ref "R17") (pin "2") (pinfunction "2_2") (pintype "passive"))
      (node (ref "R22") (pin "2") (pinfunction "2_2") (pintype "passive"))
      (node (ref "TJA1") (pin "8") (pinfunction "S_8") (pintype "passive"))
      (node (ref "TPS1") (pin "6") (pinfunction "GND_6") (pintype "passive"))
      (node (ref "U1") (pin "7") (pinfunction "Vcc_7") (pintype "power_in"))
      (node (ref "U1") (pin "8") (pinfunction "Sout_8") (pintype "power_in"))
    )
    (net (code "82") (name "VIN") (class "Default")
      (node (ref "C22") (pin "1") (pinfunction "1_1") (pintype "passive"))
      (node (ref "C24") (pin "1") (pinfunction "1_1") (pintype "passive"))
      (node (ref "C25") (pin "1") (pinfunction "1_1") (pintype "passive"))
      (node (ref "MOS1") (pin "4") (pinfunction "D_4") (pintype "passive"))
      (node (ref "MOS3") (pin "4") (pinfunction "D_4") (pintype "passive"))
      (node (ref "MOS5") (pin "4") (pinfunction "D_4") (pintype "passive"))
      (node (ref "P5") (pin "1") (pinfunction "1_1") (pintype "passive"))
      (node (ref "R23") (pin "2") (pinfunction "2_2") (pintype "passive"))
      (node (ref "TPS1") (pin "7") (pinfunction "VIN_7") (pintype "passive"))
    )
    (net (code "83") (name "unconnected-(MCU1-PA6{slash}SPI1_MISO-Pad22)") (class "Default")
      (node (ref "MCU1") (pin "22") (pinfunction "PA6/SPI1_MISO_22") (pintype "passive"))
    )
    (net (code "84") (name "unconnected-(MCU1-PA7{slash}SPI1_MOSI-Pad23)") (class "Default")
      (node (ref "MCU1") (pin "23") (pinfunction "PA7/SPI1_MOSI_23") (pintype "passive"))
    )
    (net (code "85") (name "unconnected-(MCU1-PA8{slash}USART1_CK-Pad41)") (class "Default")
      (node (ref "MCU1") (pin "41") (pinfunction "PA8/USART1_CK_41") (pintype "passive"))
    )
    (net (code "86") (name "unconnected-(MCU1-PA9{slash}USART1_TX-Pad42)") (class "Default")
      (node (ref "MCU1") (pin "42") (pinfunction "PA9/USART1_TX_42") (pintype "passive"))
    )
    (net (code "87") (name "unconnected-(MCU1-PA10{slash}USART1_RX-Pad43)") (class "Default")
      (node (ref "MCU1") (pin "43") (pinfunction "PA10/USART1_RX_43") (pintype "passive"))
    )
    (net (code "88") (name "unconnected-(MCU1-PB8{slash}TIM4_CH3-Pad61)") (class "Default")
      (node (ref "MCU1") (pin "61") (pinfunction "PB8/TIM4_CH3_61") (pintype "passive"))
    )
    (net (code "89") (name "unconnected-(MCU1-PB9{slash}TIM4_CH4-Pad62)") (class "Default")
      (node (ref "MCU1") (pin "62") (pinfunction "PB9/TIM4_CH4_62") (pintype "passive"))
    )
    (net (code "90") (name "unconnected-(MCU1-PC0{slash}ADC10-Pad8)") (class "Default")
      (node (ref "MCU1") (pin "8") (pinfunction "PC0/ADC10_8") (pintype "passive"))
    )
    (net (code "91") (name "unconnected-(MCU1-PC1{slash}ADC11-Pad9)") (class "Default")
      (node (ref "MCU1") (pin "9") (pinfunction "PC1/ADC11_9") (pintype "passive"))
    )
    (net (code "92") (name "unconnected-(MCU1-PC2{slash}ADC12-Pad10)") (class "Default")
      (node (ref "MCU1") (pin "10") (pinfunction "PC2/ADC12_10") (pintype "passive"))
    )
    (net (code "93") (name "unconnected-(MCU1-PC3{slash}ADC13-Pad11)") (class "Default")
      (node (ref "MCU1") (pin "11") (pinfunction "PC3/ADC13_11") (pintype "passive"))
    )
    (net (code "94") (name "unconnected-(MCU1-PC4{slash}ADC14-Pad24)") (class "Default")
      (node (ref "MCU1") (pin "24") (pinfunction "PC4/ADC14_24") (pintype "passive"))
    )
    (net (code "95") (name "unconnected-(MCU1-PC5{slash}ADC15-Pad25)") (class "Default")
      (node (ref "MCU1") (pin "25") (pinfunction "PC5/ADC15_25") (pintype "passive"))
    )
    (net (code "96") (name "unconnected-(MCU1-PC7-Pad38)") (class "Default")
      (node (ref "MCU1") (pin "38") (pinfunction "PC7_38") (pintype "passive"))
    )
    (net (code "97") (name "unconnected-(MCU1-PC8-Pad39)") (class "Default")
      (node (ref "MCU1") (pin "39") (pinfunction "PC8_39") (pintype "passive"))
    )
    (net (code "98") (name "unconnected-(MCU1-PC9-Pad40)") (class "Default")
      (node (ref "MCU1") (pin "40") (pinfunction "PC9_40") (pintype "passive"))
    )
    (net (code "99") (name "unconnected-(TJA1-Vref-Pad5)") (class "Default")
      (node (ref "TJA1") (pin "5") (pinfunction "Vref_5") (pintype "passive"))
    )
    (net (code "100") (name "unconnected-(TPS1-ENA-Pad5)") (class "Default")
      (node (ref "TPS1") (pin "5") (pinfunction "ENA_5") (pintype "passive"))
    )
    (net (code "101") (name "unconnected-(TPS1-NC-Pad2)") (class "Default")
      (node (ref "TPS1") (pin "2") (pinfunction "NC_2") (pintype "passive"))
    )
    (net (code "102") (name "unconnected-(TPS1-NC-Pad3)") (class "Default")
      (node (ref "TPS1") (pin "3") (pinfunction "NC_3") (pintype "passive"))
    )
    (net (code "103") (name "unconnected-(U1-C-Pad10)") (class "Default")
      (node (ref "U1") (pin "10") (pinfunction "C_10") (pintype "power_in"))
    )
  )
)
